# SCANOPCB_V2.net
KiCad netlist of a schematic drawn in EAGLE
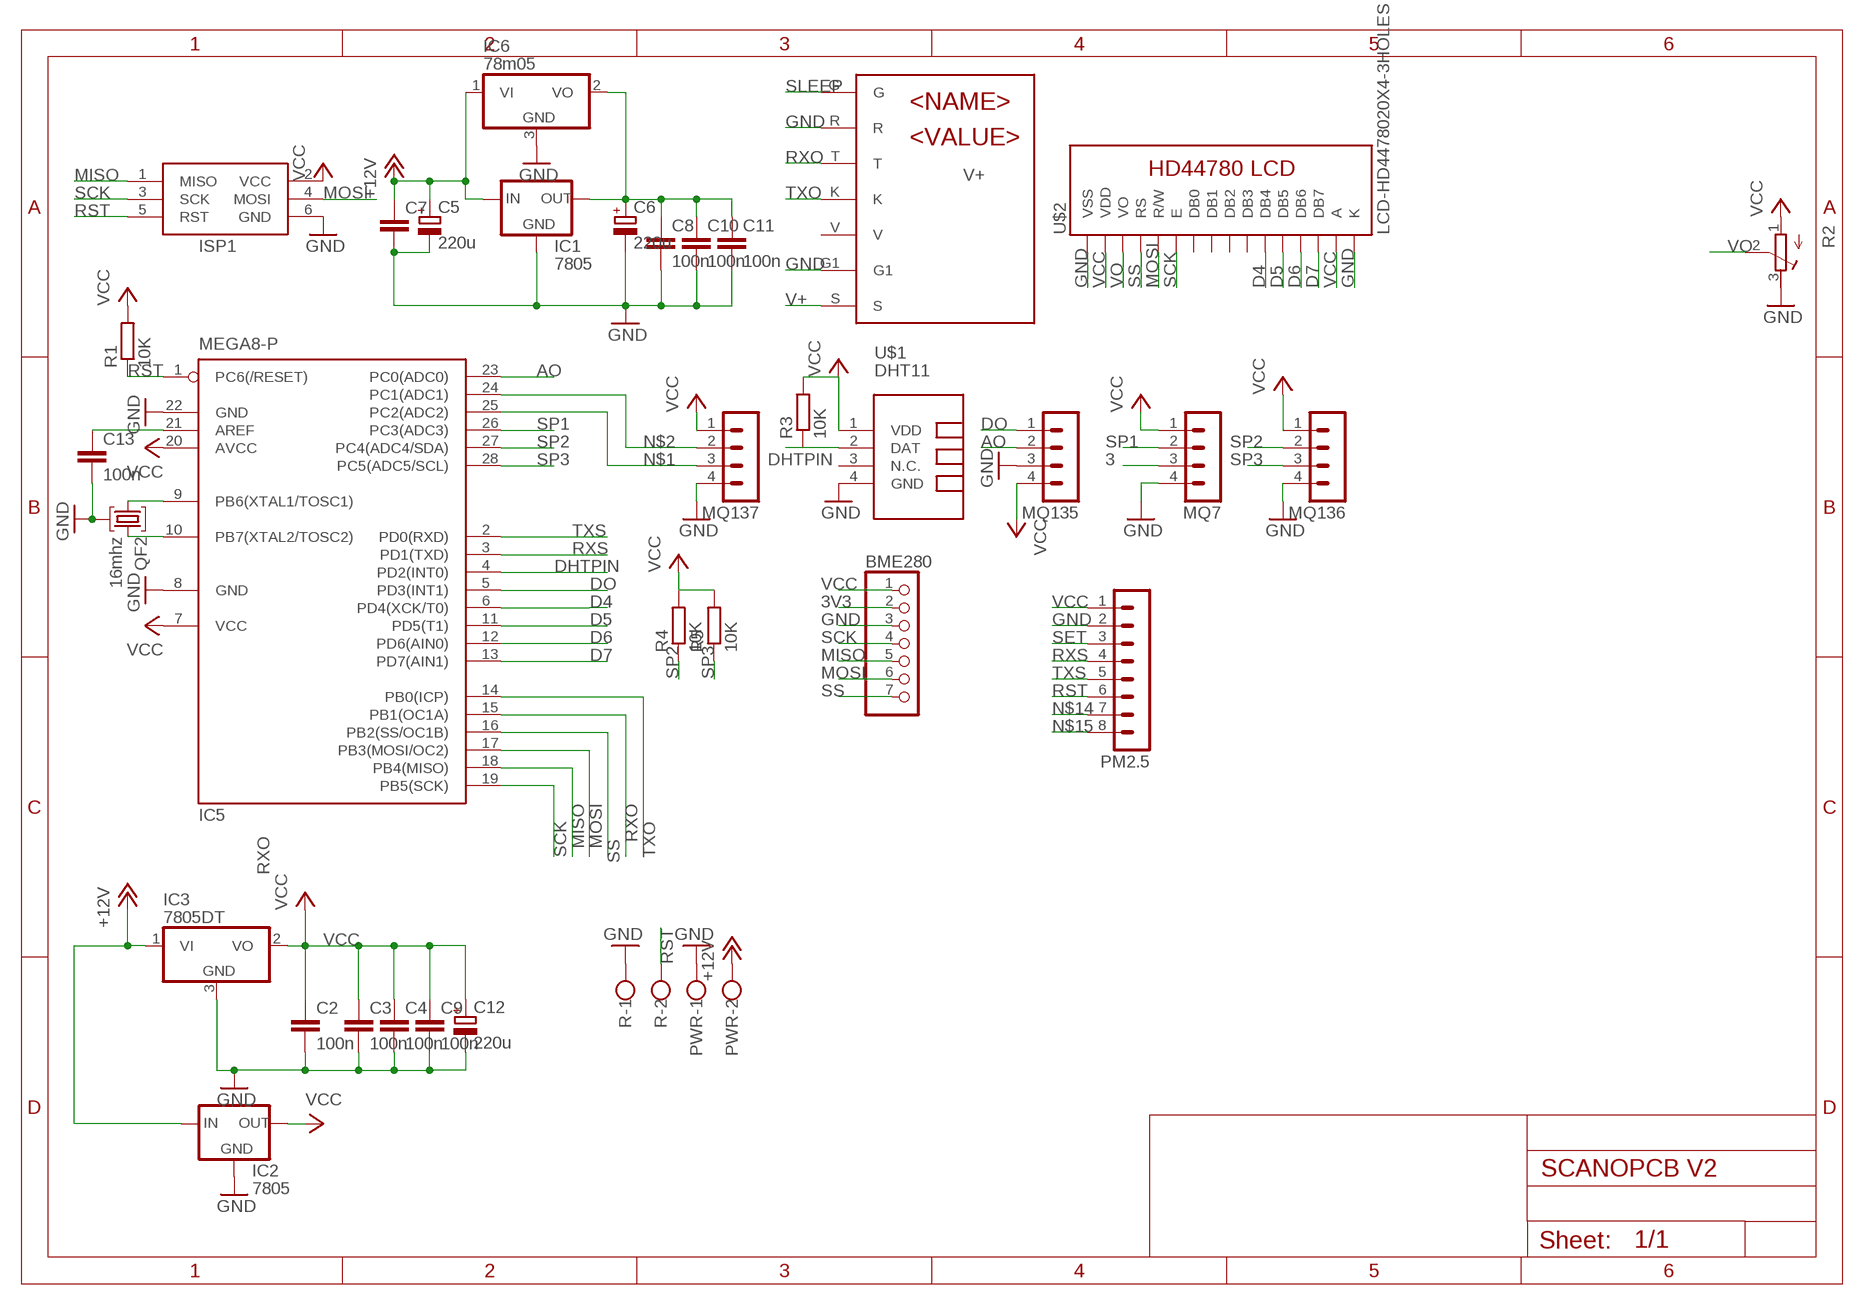
[diagram p0: schematic, sheet 1]

(export (version "E")
  (design (tool "Eeschema 10.0.6"))
  (components
    (comp (ref "BME280")
      (value "PINHD-1X7")
      (footprint "eagle-import:1X07")
      (libsource (lib "eagle-import") (part "PINHD-1X7"))
    )
    (comp (ref "C2")
      (value "100n")
      (footprint "eagle-import:C1206")
      (libsource (lib "eagle-import") (part "C-EUC1206"))
    )
    (comp (ref "C3")
      (value "100n")
      (footprint "eagle-import:C1206")
      (libsource (lib "eagle-import") (part "C-EUC1206"))
    )
    (comp (ref "C4")
      (value "100n")
      (footprint "eagle-import:C1206")
      (libsource (lib "eagle-import") (part "C-EUC1206"))
    )
    (comp (ref "C5")
      (value "220u")
      (footprint "eagle-import:E5-8,5")
      (libsource (lib "eagle-import") (part "CPOL-EUE5-8.5"))
    )
    (comp (ref "C6")
      (value "220u")
      (footprint "eagle-import:E5-8,5")
      (libsource (lib "eagle-import") (part "CPOL-EUE5-8.5"))
    )
    (comp (ref "C7")
      (value "C-EUC1206")
      (footprint "eagle-import:C1206")
      (libsource (lib "eagle-import") (part "C-EUC1206"))
    )
    (comp (ref "C8")
      (value "100n")
      (footprint "eagle-import:C1206")
      (libsource (lib "eagle-import") (part "C-EUC1206"))
    )
    (comp (ref "C9")
      (value "100n")
      (footprint "eagle-import:C1206")
      (libsource (lib "eagle-import") (part "C-EUC1206"))
    )
    (comp (ref "C10")
      (value "100n")
      (footprint "eagle-import:C1206")
      (libsource (lib "eagle-import") (part "C-EUC1206"))
    )
    (comp (ref "C11")
      (value "100n")
      (footprint "eagle-import:C1206")
      (libsource (lib "eagle-import") (part "C-EUC1206"))
    )
    (comp (ref "C12")
      (value "220u")
      (footprint "eagle-import:E5-8,5")
      (libsource (lib "eagle-import") (part "CPOL-EUE5-8.5"))
    )
    (comp (ref "C13")
      (value "100n")
      (footprint "eagle-import:C1206")
      (libsource (lib "eagle-import") (part "C-EUC1206"))
    )
    (comp (ref "IC1")
      (value "7805")
      (footprint "eagle-import:78XXL")
      (libsource (lib "eagle-import") (part "78XXL"))
    )
    (comp (ref "IC2")
      (value "7805")
      (footprint "eagle-import:78XXL")
      (libsource (lib "eagle-import") (part "78XXL"))
    )
    (comp (ref "IC3")
      (value "7805DT")
      (footprint "eagle-import:TO252")
      (libsource (lib "eagle-import") (part "linear_78DT05"))
    )
    (comp (ref "IC5")
      (value "MEGA8-P")
      (footprint "eagle-import:DIL28-3")
      (libsource (lib "eagle-import") (part "MEGA8-P"))
    )
    (comp (ref "IC6")
      (value "78m05")
      (footprint "eagle-import:TO252")
      (libsource (lib "eagle-import") (part "78DT12"))
    )
    (comp (ref "ISP1")
      (value "AVRISP-6")
      (footprint "eagle-import:AVRISP")
      (libsource (lib "eagle-import") (part "AVRISP-6"))
    )
    (comp (ref "MQ7")
      (value "MA04-1")
      (footprint "eagle-import:MA04-1")
      (libsource (lib "eagle-import") (part "MA04-1"))
    )
    (comp (ref "MQ135")
      (value "MA04-1")
      (footprint "eagle-import:MA04-1")
      (libsource (lib "eagle-import") (part "MA04-1"))
    )
    (comp (ref "MQ136")
      (value "MA04-1")
      (footprint "eagle-import:MA04-1")
      (libsource (lib "eagle-import") (part "MA04-1"))
    )
    (comp (ref "MQ137")
      (value "MA04-1")
      (footprint "eagle-import:MA04-1")
      (libsource (lib "eagle-import") (part "MA04-1"))
    )
    (comp (ref "PM2.5")
      (value "MA08-1")
      (footprint "eagle-import:MA08-1")
      (libsource (lib "eagle-import") (part "MA08-1"))
    )
    (comp (ref "PWR")
      (value "W237-102")
      (footprint "eagle-import:W237-102")
      (fields (field (name "MPN") "237-102"))
      (libsource (lib "eagle-import") (part "W237-102"))
    )
    (comp (ref "QF2")
      (value "16mhz")
      (footprint "eagle-import:HC49U")
      (libsource (lib "eagle-import") (part "49M8AHC49T"))
    )
    (comp (ref "R")
      (value "W237-102")
      (footprint "eagle-import:W237-102")
      (fields (field (name "MPN") "237-102"))
      (libsource (lib "eagle-import") (part "W237-102"))
    )
    (comp (ref "R1")
      (value "10K")
      (footprint "eagle-import:R1206")
      (libsource (lib "eagle-import") (part "R-EU_R1206"))
    )
    (comp (ref "R2")
      (value "R-TRIMM64P")
      (footprint "eagle-import:RTRIM64P")
      (libsource (lib "eagle-import") (part "R-TRIMM64P"))
    )
    (comp (ref "R3")
      (value "10K")
      (footprint "eagle-import:R1206")
      (libsource (lib "eagle-import") (part "R-EU_R1206"))
    )
    (comp (ref "R4")
      (value "10K")
      (footprint "eagle-import:R1206")
      (libsource (lib "eagle-import") (part "R-EU_R1206"))
    )
    (comp (ref "R5")
      (value "10K")
      (footprint "eagle-import:R1206")
      (libsource (lib "eagle-import") (part "R-EU_R1206"))
    )
    (comp (ref "SIM7000")
      (value "SIM7000")
      (footprint "eagle-import:SIM7000")
      (libsource (lib "eagle-import") (part "SIM7000"))
    )
    (comp (ref "U$1")
      (value "DHT11")
      (footprint "eagle-import:TEMP-HUM-SENSOR-DHT11")
      (libsource (lib "eagle-import") (part "TEMP-HUM-SENSOR-DHT11"))
    )
    (comp (ref "U$2")
      (value "LCD-HD4478020X4-3HOLES")
      (footprint "eagle-import:LCD-20X4-3HOLES")
      (libsource (lib "eagle-import") (part "LCD-HD4478020X4-3HOLES"))
    )
  )
  (nets
    (net (code "1") (name "+12V") (class "Default")
      (node (ref "C5") (pin "+") (pinfunction "+_+") (pintype "passive"))
      (node (ref "C7") (pin "1") (pinfunction "1_1") (pintype "passive"))
      (node (ref "IC1") (pin "IN") (pinfunction "IN_IN") (pintype "input"))
      (node (ref "IC2") (pin "IN") (pinfunction "IN_IN") (pintype "input"))
      (node (ref "IC3") (pin "1") (pinfunction "VI_1") (pintype "input"))
      (node (ref "IC6") (pin "1") (pinfunction "VI_1") (pintype "input"))
      (node (ref "PWR") (pin "2") (pinfunction "KL_2") (pintype "passive"))
    )
    (net (code "2") (name "/3") (class "Default")
      (node (ref "MQ7") (pin "3") (pinfunction "3_3") (pintype "passive"))
    )
    (net (code "3") (name "/3V3") (class "Default")
      (node (ref "BME280") (pin "2") (pinfunction "2_2") (pintype "passive"))
    )
    (net (code "4") (name "/AO") (class "Default")
      (node (ref "IC5") (pin "23") (pinfunction "PC0(ADC0)_23") (pintype "bidirectional"))
      (node (ref "MQ135") (pin "2") (pinfunction "2_2") (pintype "passive"))
    )
    (net (code "5") (name "/D4") (class "Default")
      (node (ref "IC5") (pin "6") (pinfunction "PD4(XCK/T0)_6") (pintype "bidirectional"))
      (node (ref "U$2") (pin "P$11") (pinfunction "DB4_P$11") (pintype "bidirectional"))
    )
    (net (code "6") (name "/D5") (class "Default")
      (node (ref "IC5") (pin "11") (pinfunction "PD5(T1)_11") (pintype "bidirectional"))
      (node (ref "U$2") (pin "P$12") (pinfunction "DB5_P$12") (pintype "bidirectional"))
    )
    (net (code "7") (name "/D6") (class "Default")
      (node (ref "IC5") (pin "12") (pinfunction "PD6(AIN0)_12") (pintype "bidirectional"))
      (node (ref "U$2") (pin "P$13") (pinfunction "DB6_P$13") (pintype "bidirectional"))
    )
    (net (code "8") (name "/D7") (class "Default")
      (node (ref "IC5") (pin "13") (pinfunction "PD7(AIN1)_13") (pintype "bidirectional"))
      (node (ref "U$2") (pin "P$14") (pinfunction "DB7_P$14") (pintype "bidirectional"))
    )
    (net (code "9") (name "/DHTPIN") (class "Default")
      (node (ref "IC5") (pin "4") (pinfunction "PD2(INT0)_4") (pintype "bidirectional"))
      (node (ref "R3") (pin "1") (pinfunction "1_1") (pintype "passive"))
      (node (ref "U$1") (pin "2") (pinfunction "DAT_2") (pintype "bidirectional"))
    )
    (net (code "10") (name "/DO") (class "Default")
      (node (ref "IC5") (pin "5") (pinfunction "PD3(INT1)_5") (pintype "bidirectional"))
      (node (ref "MQ135") (pin "1") (pinfunction "1_1") (pintype "passive"))
    )
    (net (code "11") (name "/MISO") (class "Default")
      (node (ref "BME280") (pin "5") (pinfunction "5_5") (pintype "passive"))
      (node (ref "IC5") (pin "18") (pinfunction "PB4(MISO)_18") (pintype "bidirectional"))
      (node (ref "ISP1") (pin "1") (pinfunction "MISO_1") (pintype "input"))
    )
    (net (code "12") (name "/MOSI") (class "Default")
      (node (ref "BME280") (pin "6") (pinfunction "6_6") (pintype "passive"))
      (node (ref "IC5") (pin "17") (pinfunction "PB3(MOSI/OC2)_17") (pintype "bidirectional"))
      (node (ref "ISP1") (pin "4") (pinfunction "MOSI_4") (pintype "output"))
      (node (ref "U$2") (pin "P$5") (pinfunction "R/W_P$5") (pintype "input"))
    )
    (net (code "13") (name "/N$1") (class "Default")
      (node (ref "IC5") (pin "25") (pinfunction "PC2(ADC2)_25") (pintype "bidirectional"))
      (node (ref "MQ137") (pin "3") (pinfunction "3_3") (pintype "passive"))
    )
    (net (code "14") (name "/N$2") (class "Default")
      (node (ref "IC5") (pin "24") (pinfunction "PC1(ADC1)_24") (pintype "bidirectional"))
      (node (ref "MQ137") (pin "2") (pinfunction "2_2") (pintype "passive"))
    )
    (net (code "15") (name "/N$14") (class "Default")
      (node (ref "PM2.5") (pin "7") (pinfunction "7_7") (pintype "passive"))
    )
    (net (code "16") (name "/N$15") (class "Default")
      (node (ref "PM2.5") (pin "8") (pinfunction "8_8") (pintype "passive"))
    )
    (net (code "17") (name "/RST") (class "Default")
      (node (ref "IC5") (pin "1") (pinfunction "PC6(/RESET)_1") (pintype "bidirectional"))
      (node (ref "ISP1") (pin "5") (pinfunction "RST_5") (pintype "output"))
      (node (ref "PM2.5") (pin "6") (pinfunction "6_6") (pintype "passive"))
      (node (ref "R") (pin "2") (pinfunction "KL_2") (pintype "passive"))
      (node (ref "R1") (pin "1") (pinfunction "1_1") (pintype "passive"))
    )
    (net (code "18") (name "/RXO") (class "Default")
      (node (ref "IC5") (pin "15") (pinfunction "PB1(OC1A)_15") (pintype "bidirectional"))
      (node (ref "SIM7000") (pin "T") (pinfunction "T_T") (pintype "bidirectional"))
    )
    (net (code "19") (name "/RXS") (class "Default")
      (node (ref "IC5") (pin "3") (pinfunction "PD1(TXD)_3") (pintype "bidirectional"))
      (node (ref "PM2.5") (pin "4") (pinfunction "4_4") (pintype "passive"))
    )
    (net (code "20") (name "/SCK") (class "Default")
      (node (ref "BME280") (pin "4") (pinfunction "4_4") (pintype "passive"))
      (node (ref "IC5") (pin "19") (pinfunction "PB5(SCK)_19") (pintype "bidirectional"))
      (node (ref "ISP1") (pin "3") (pinfunction "SCK_3") (pintype "output"))
      (node (ref "U$2") (pin "P$6") (pinfunction "E_P$6") (pintype "input"))
    )
    (net (code "21") (name "/SET") (class "Default")
      (node (ref "PM2.5") (pin "3") (pinfunction "3_3") (pintype "passive"))
    )
    (net (code "22") (name "/SLEEP") (class "Default")
      (node (ref "SIM7000") (pin "G") (pinfunction "G_G") (pintype "bidirectional"))
    )
    (net (code "23") (name "/SP1") (class "Default")
      (node (ref "IC5") (pin "26") (pinfunction "PC3(ADC3)_26") (pintype "bidirectional"))
      (node (ref "MQ7") (pin "2") (pinfunction "2_2") (pintype "passive"))
    )
    (net (code "24") (name "/SP2") (class "Default")
      (node (ref "IC5") (pin "27") (pinfunction "PC4(ADC4/SDA)_27") (pintype "bidirectional"))
      (node (ref "MQ136") (pin "2") (pinfunction "2_2") (pintype "passive"))
      (node (ref "R4") (pin "1") (pinfunction "1_1") (pintype "passive"))
    )
    (net (code "25") (name "/SP3") (class "Default")
      (node (ref "IC5") (pin "28") (pinfunction "PC5(ADC5/SCL)_28") (pintype "bidirectional"))
      (node (ref "MQ136") (pin "3") (pinfunction "3_3") (pintype "passive"))
      (node (ref "R5") (pin "1") (pinfunction "1_1") (pintype "passive"))
    )
    (net (code "26") (name "/SS") (class "Default")
      (node (ref "BME280") (pin "7") (pinfunction "7_7") (pintype "passive"))
      (node (ref "IC5") (pin "16") (pinfunction "PB2(SS/OC1B)_16") (pintype "bidirectional"))
      (node (ref "U$2") (pin "P$4") (pinfunction "RS_P$4") (pintype "input"))
    )
    (net (code "27") (name "/TXO") (class "Default")
      (node (ref "IC5") (pin "14") (pinfunction "PB0(ICP)_14") (pintype "bidirectional"))
      (node (ref "SIM7000") (pin "K") (pinfunction "K_K") (pintype "bidirectional"))
    )
    (net (code "28") (name "/TXS") (class "Default")
      (node (ref "IC5") (pin "2") (pinfunction "PD0(RXD)_2") (pintype "bidirectional"))
      (node (ref "PM2.5") (pin "5") (pinfunction "5_5") (pintype "passive"))
    )
    (net (code "29") (name "/V+") (class "Default")
      (node (ref "C10") (pin "1") (pinfunction "1_1") (pintype "passive"))
      (node (ref "C11") (pin "1") (pinfunction "1_1") (pintype "passive"))
      (node (ref "C6") (pin "+") (pinfunction "+_+") (pintype "passive"))
      (node (ref "C8") (pin "1") (pinfunction "1_1") (pintype "passive"))
      (node (ref "IC1") (pin "OUT") (pinfunction "OUT_OUT") (pintype "passive"))
      (node (ref "IC6") (pin "2") (pinfunction "VO_2") (pintype "passive"))
      (node (ref "SIM7000") (pin "S") (pinfunction "S_S") (pintype "bidirectional"))
    )
    (net (code "30") (name "/VO") (class "Default")
      (node (ref "R2") (pin "2") (pinfunction "S_2") (pintype "passive"))
      (node (ref "U$2") (pin "P$3") (pinfunction "VO_P$3") (pintype "bidirectional"))
    )
    (net (code "31") (name "GND") (class "Default")
      (node (ref "BME280") (pin "3") (pinfunction "3_3") (pintype "passive"))
      (node (ref "C10") (pin "2") (pinfunction "2_2") (pintype "passive"))
      (node (ref "C11") (pin "2") (pinfunction "2_2") (pintype "passive"))
      (node (ref "C12") (pin "-") (pinfunction "-_-") (pintype "passive"))
      (node (ref "C13") (pin "2") (pinfunction "2_2") (pintype "passive"))
      (node (ref "C2") (pin "2") (pinfunction "2_2") (pintype "passive"))
      (node (ref "C3") (pin "2") (pinfunction "2_2") (pintype "passive"))
      (node (ref "C4") (pin "2") (pinfunction "2_2") (pintype "passive"))
      (node (ref "C5") (pin "-") (pinfunction "-_-") (pintype "passive"))
      (node (ref "C6") (pin "-") (pinfunction "-_-") (pintype "passive"))
      (node (ref "C7") (pin "2") (pinfunction "2_2") (pintype "passive"))
      (node (ref "C8") (pin "2") (pinfunction "2_2") (pintype "passive"))
      (node (ref "C9") (pin "2") (pinfunction "2_2") (pintype "passive"))
      (node (ref "IC1") (pin "GND") (pinfunction "GND_GND") (pintype "input"))
      (node (ref "IC2") (pin "GND") (pinfunction "GND_GND") (pintype "input"))
      (node (ref "IC3") (pin "3") (pinfunction "GND_3") (pintype "passive"))
      (node (ref "IC5") (pin "22") (pinfunction "GND_22") (pintype "power_in"))
      (node (ref "IC5") (pin "8") (pinfunction "GND_8") (pintype "power_in"))
      (node (ref "IC6") (pin "3") (pinfunction "GND_3") (pintype "passive"))
      (node (ref "ISP1") (pin "6") (pinfunction "GND_6") (pintype "power_in"))
      (node (ref "MQ135") (pin "3") (pinfunction "3_3") (pintype "passive"))
      (node (ref "MQ136") (pin "4") (pinfunction "4_4") (pintype "passive"))
      (node (ref "MQ137") (pin "4") (pinfunction "4_4") (pintype "passive"))
      (node (ref "MQ7") (pin "4") (pinfunction "4_4") (pintype "passive"))
      (node (ref "PM2.5") (pin "2") (pinfunction "2_2") (pintype "passive"))
      (node (ref "PWR") (pin "1") (pinfunction "KL_1") (pintype "passive"))
      (node (ref "QF2") (pin "2") (pinfunction "2_2") (pintype "passive"))
      (node (ref "R") (pin "1") (pinfunction "KL_1") (pintype "passive"))
      (node (ref "R2") (pin "3") (pinfunction "E_3") (pintype "passive"))
      (node (ref "SIM7000") (pin "G1") (pinfunction "G1_G1") (pintype "bidirectional"))
      (node (ref "SIM7000") (pin "R") (pinfunction "R_R") (pintype "bidirectional"))
      (node (ref "U$1") (pin "4") (pinfunction "GND_4") (pintype "power_in"))
      (node (ref "U$2") (pin "P$1") (pinfunction "VSS_P$1") (pintype "power_in"))
      (node (ref "U$2") (pin "P$16") (pinfunction "K_P$16") (pintype "power_in"))
    )
    (net (code "32") (name "Net-(IC5-AREF)") (class "Default")
      (node (ref "C13") (pin "1") (pinfunction "1_1") (pintype "passive"))
      (node (ref "IC5") (pin "21") (pinfunction "AREF_21") (pintype "passive"))
    )
    (net (code "33") (name "Net-(IC5-PB6(XTAL1{slash}TOSC1))") (class "Default")
      (node (ref "IC5") (pin "9") (pinfunction "PB6(XTAL1/TOSC1)_9") (pintype "bidirectional"))
      (node (ref "QF2") (pin "1") (pinfunction "1_1") (pintype "passive"))
    )
    (net (code "34") (name "Net-(IC5-PB7(XTAL2{slash}TOSC2))") (class "Default")
      (node (ref "IC5") (pin "10") (pinfunction "PB7(XTAL2/TOSC2)_10") (pintype "bidirectional"))
      (node (ref "QF2") (pin "3") (pinfunction "3_3") (pintype "passive"))
    )
    (net (code "35") (name "VCC") (class "Default")
      (node (ref "BME280") (pin "1") (pinfunction "1_1") (pintype "passive"))
      (node (ref "C12") (pin "+") (pinfunction "+_+") (pintype "passive"))
      (node (ref "C2") (pin "1") (pinfunction "1_1") (pintype "passive"))
      (node (ref "C3") (pin "1") (pinfunction "1_1") (pintype "passive"))
      (node (ref "C4") (pin "1") (pinfunction "1_1") (pintype "passive"))
      (node (ref "C9") (pin "1") (pinfunction "1_1") (pintype "passive"))
      (node (ref "IC2") (pin "OUT") (pinfunction "OUT_OUT") (pintype "passive"))
      (node (ref "IC3") (pin "2") (pinfunction "VO_2") (pintype "passive"))
      (node (ref "IC5") (pin "20") (pinfunction "AVCC_20") (pintype "power_in"))
      (node (ref "IC5") (pin "7") (pinfunction "VCC_7") (pintype "power_in"))
      (node (ref "ISP1") (pin "2") (pinfunction "VCC_2") (pintype "power_in"))
      (node (ref "MQ135") (pin "4") (pinfunction "4_4") (pintype "passive"))
      (node (ref "MQ136") (pin "1") (pinfunction "1_1") (pintype "passive"))
      (node (ref "MQ137") (pin "1") (pinfunction "1_1") (pintype "passive"))
      (node (ref "MQ7") (pin "1") (pinfunction "1_1") (pintype "passive"))
      (node (ref "PM2.5") (pin "1") (pinfunction "1_1") (pintype "passive"))
      (node (ref "R1") (pin "2") (pinfunction "2_2") (pintype "passive"))
      (node (ref "R2") (pin "1") (pinfunction "A_1") (pintype "passive"))
      (node (ref "R3") (pin "2") (pinfunction "2_2") (pintype "passive"))
      (node (ref "R4") (pin "2") (pinfunction "2_2") (pintype "passive"))
      (node (ref "R5") (pin "2") (pinfunction "2_2") (pintype "passive"))
      (node (ref "U$1") (pin "1") (pinfunction "VDD_1") (pintype "power_in"))
      (node (ref "U$2") (pin "P$15") (pinfunction "A_P$15") (pintype "power_in"))
      (node (ref "U$2") (pin "P$2") (pinfunction "VDD_P$2") (pintype "power_in"))
    )
    (net (code "36") (name "unconnected-(SIM7000-PadV)") (class "Default")
      (node (ref "SIM7000") (pin "V") (pinfunction "V_V") (pintype "bidirectional"))
    )
    (net (code "37") (name "unconnected-(U$1-N.C.-Pad3)") (class "Default")
      (node (ref "U$1") (pin "3") (pinfunction "N.C._3") (pintype "passive"))
    )
    (net (code "38") (name "unconnected-(U$2-DB0-PadP$7)") (class "Default")
      (node (ref "U$2") (pin "P$7") (pinfunction "DB0_P$7") (pintype "bidirectional"))
    )
    (net (code "39") (name "unconnected-(U$2-DB1-PadP$8)") (class "Default")
      (node (ref "U$2") (pin "P$8") (pinfunction "DB1_P$8") (pintype "bidirectional"))
    )
    (net (code "40") (name "unconnected-(U$2-DB2-PadP$9)") (class "Default")
      (node (ref "U$2") (pin "P$9") (pinfunction "DB2_P$9") (pintype "bidirectional"))
    )
    (net (code "41") (name "unconnected-(U$2-DB3-PadP$10)") (class "Default")
      (node (ref "U$2") (pin "P$10") (pinfunction "DB3_P$10") (pintype "bidirectional"))
    )
  )
)
